# NanoCore.net
KiCad netlist of a schematic drawn in EasyEDA Pro
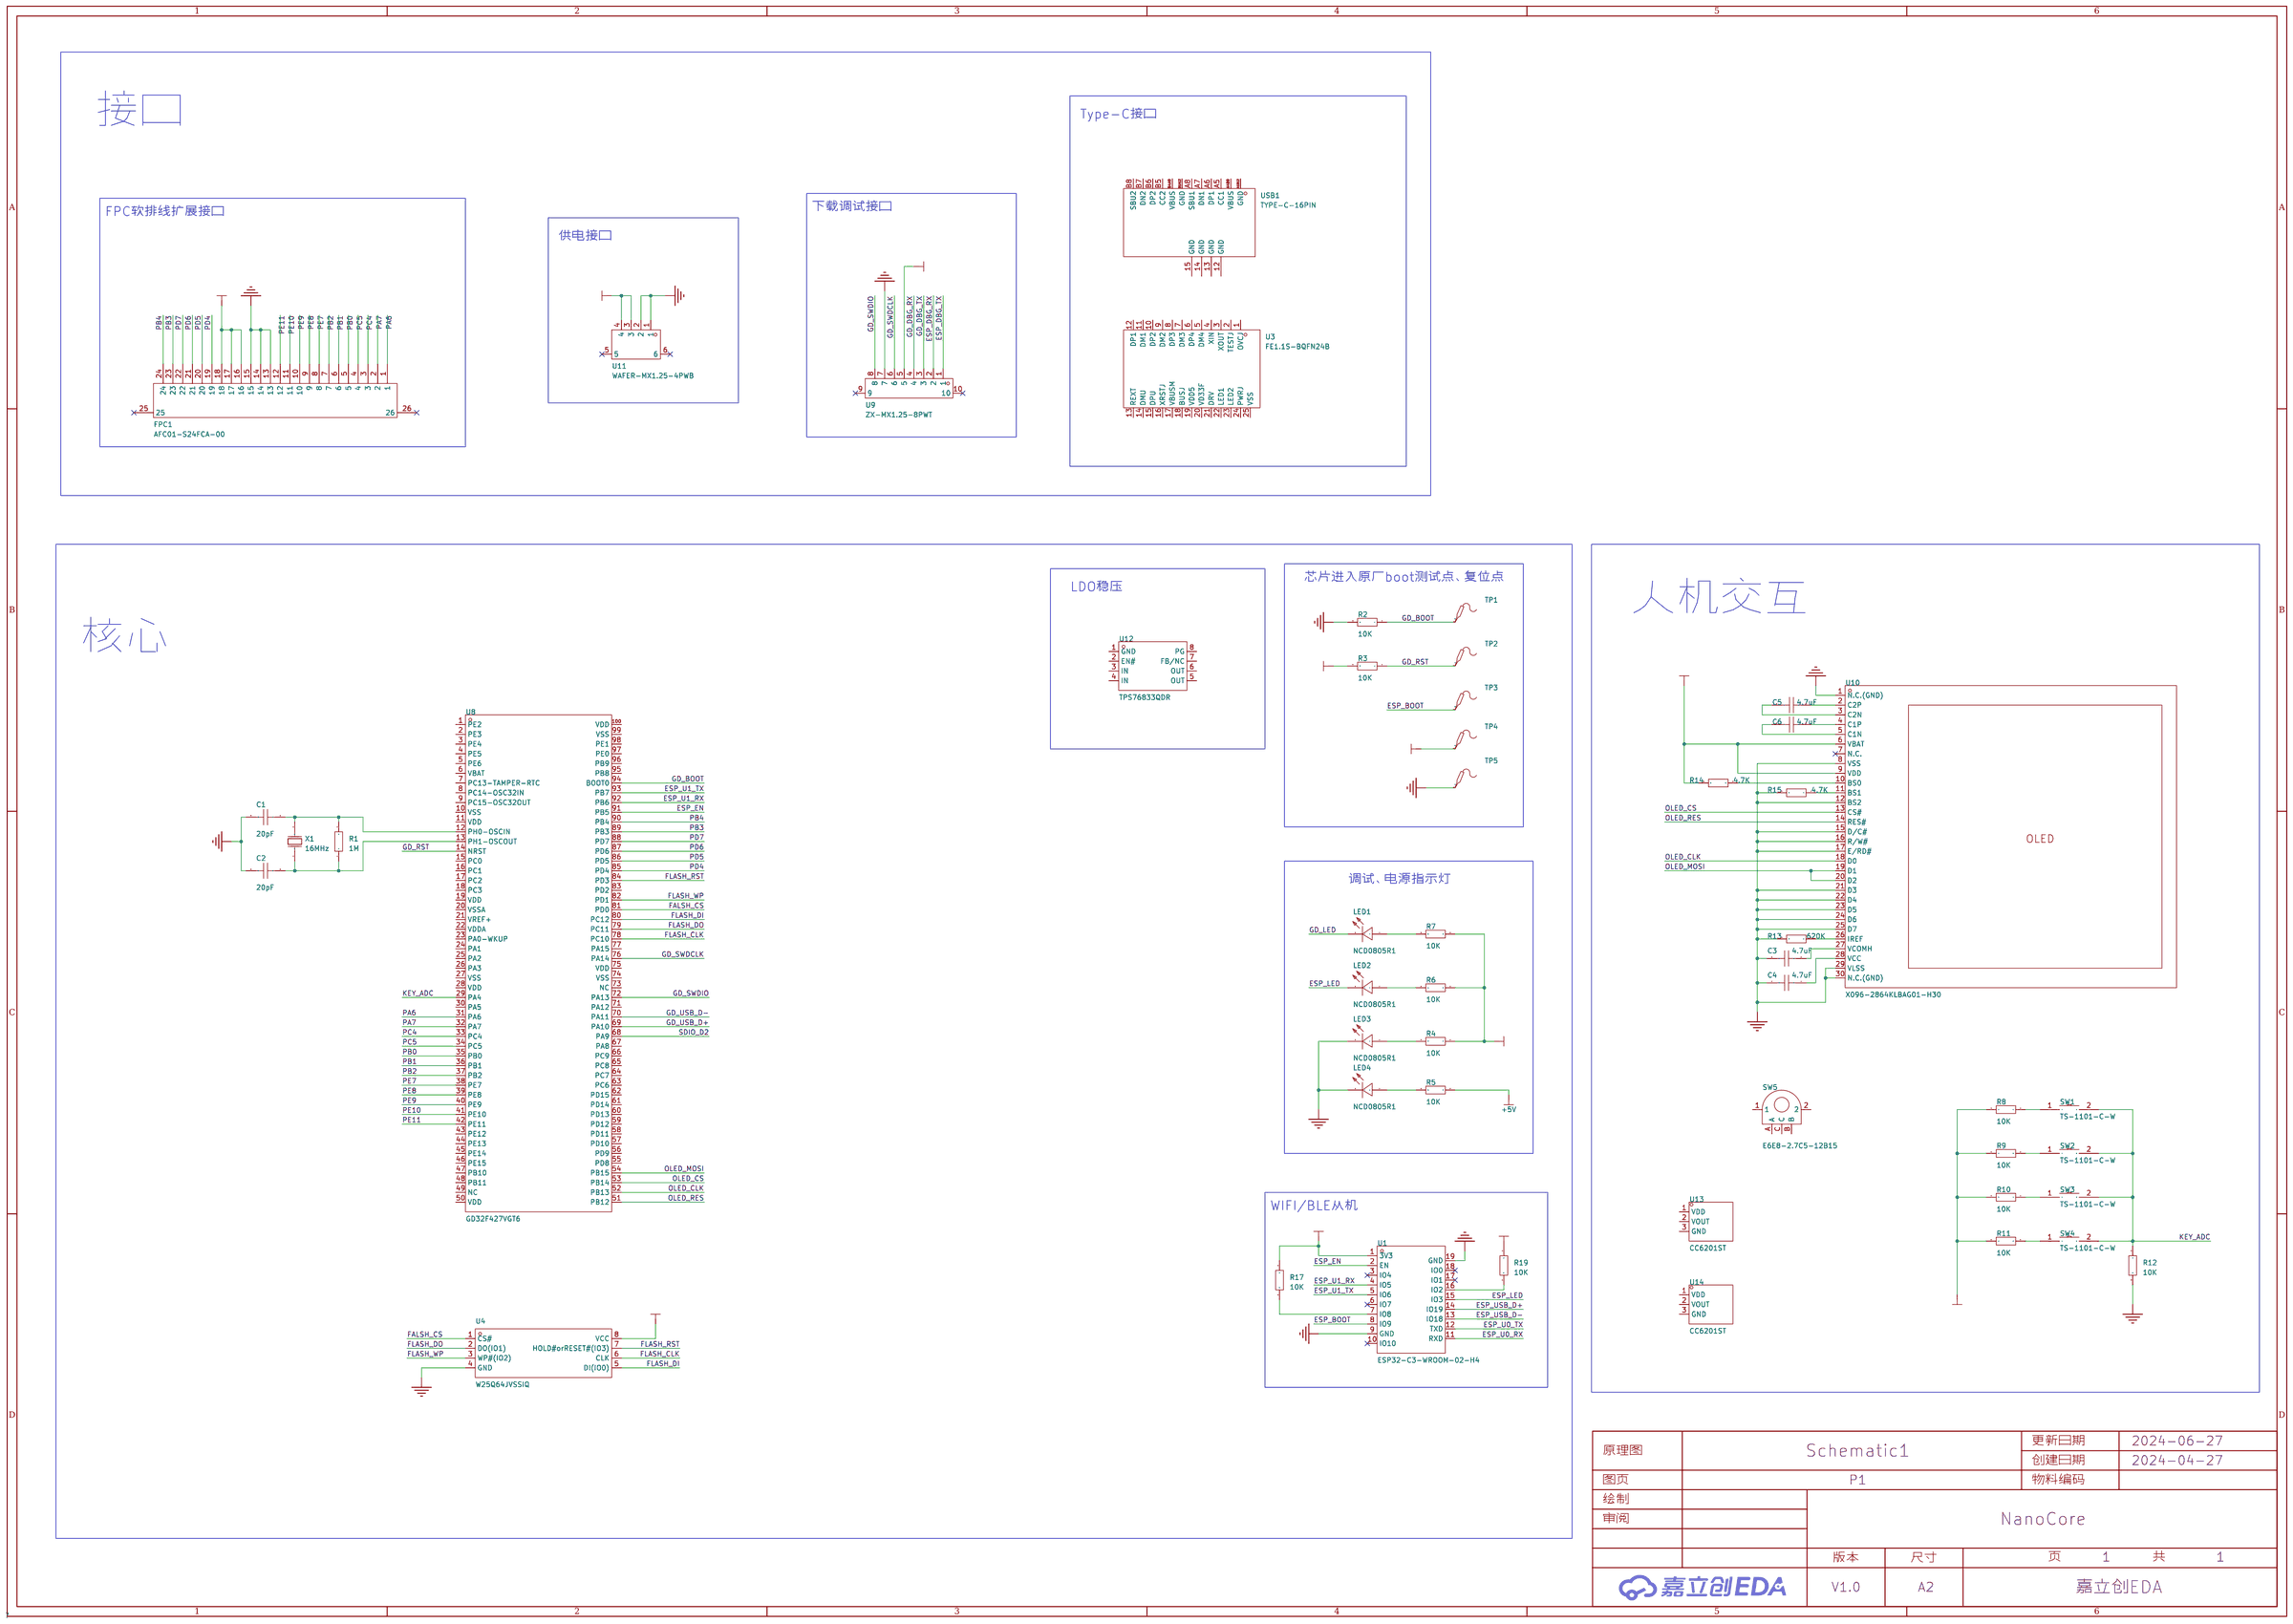
[diagram p0: schematic sheet]

(export (version "E")
  (design (tool "Eeschema 10.0.6"))
  (components
    (comp (ref "C1")
      (value "20pF")
      (footprint "easyedapro:C0603")
      (description "容值:100nF;精度:±10%;额定电压:50V;材质(温度系数):X7R;")
      (fields
        (field (name "Manufacturer Part") "CC0603KRX7R9BB104")
        (field (name "Manufacturer") "YAGEO(国巨)")
      )
      (libsource (lib "easyedapro") (part "CC0603KRX7R9BB104"))
    )
    (comp (ref "C2")
      (value "20pF")
      (footprint "easyedapro:C0603")
      (description "容值:100nF;精度:±10%;额定电压:50V;材质(温度系数):X7R;")
      (fields
        (field (name "Manufacturer Part") "CC0603KRX7R9BB104")
        (field (name "Manufacturer") "YAGEO(国巨)")
      )
      (libsource (lib "easyedapro") (part "CC0603KRX7R9BB104"))
    )
    (comp (ref "C3")
      (value "4.7uF")
      (footprint "easyedapro:C0603")
      (description "容值:100nF;精度:±10%;额定电压:50V;材质(温度系数):X7R;")
      (fields
        (field (name "Manufacturer Part") "CC0603KRX7R9BB104")
        (field (name "Manufacturer") "YAGEO(国巨)")
      )
      (libsource (lib "easyedapro") (part "CC0603KRX7R9BB104"))
    )
    (comp (ref "C4")
      (value "4.7uF")
      (footprint "easyedapro:C0603")
      (description "容值:100nF;精度:±10%;额定电压:50V;材质(温度系数):X7R;")
      (fields
        (field (name "Manufacturer Part") "CC0603KRX7R9BB104")
        (field (name "Manufacturer") "YAGEO(国巨)")
      )
      (libsource (lib "easyedapro") (part "CC0603KRX7R9BB104"))
    )
    (comp (ref "C5")
      (value "4.7uF")
      (footprint "easyedapro:C0603")
      (description "容值:100nF;精度:±10%;额定电压:50V;材质(温度系数):X7R;")
      (fields
        (field (name "Manufacturer Part") "CC0603KRX7R9BB104")
        (field (name "Manufacturer") "YAGEO(国巨)")
      )
      (libsource (lib "easyedapro") (part "CC0603KRX7R9BB104"))
    )
    (comp (ref "C6")
      (value "4.7uF")
      (footprint "easyedapro:C0603")
      (description "容值:100nF;精度:±10%;额定电压:50V;材质(温度系数):X7R;")
      (fields
        (field (name "Manufacturer Part") "CC0603KRX7R9BB104")
        (field (name "Manufacturer") "YAGEO(国巨)")
      )
      (libsource (lib "easyedapro") (part "CC0603KRX7R9BB104"))
    )
    (comp (ref "FPC1")
      (value "AFC01-S24FCA-00")
      (footprint "easyedapro:FPC-SMD_P0.50-24P_FGS-XJ-H2.0")
      (description "锁定特性:翻盖式;触点类型:下接;触点数量:24P;间距:0.5mm;安装类型:卧贴;")
      (fields (field (name "Manufacturer") "JS(钜硕电子)"))
      (libsource (lib "easyedapro") (part "AFC01-S24FCA-00"))
    )
    (comp (ref "LED1")
      (value "NCD0805R1")
      (footprint "easyedapro:LED0805-R-RD")
      (fields (field (name "Manufacturer") "国星光电"))
      (libsource (lib "easyedapro") (part "FC-2012HRK-620D"))
    )
    (comp (ref "LED2")
      (value "NCD0805R1")
      (footprint "easyedapro:LED0805-R-RD")
      (fields (field (name "Manufacturer") "国星光电"))
      (libsource (lib "easyedapro") (part "FC-2012HRK-620D"))
    )
    (comp (ref "LED3")
      (value "NCD0805R1")
      (footprint "easyedapro:LED0805-R-RD")
      (fields (field (name "Manufacturer") "国星光电"))
      (libsource (lib "easyedapro") (part "FC-2012HRK-620D"))
    )
    (comp (ref "LED4")
      (value "NCD0805R1")
      (footprint "easyedapro:LED0805-R-RD")
      (fields (field (name "Manufacturer") "国星光电"))
      (libsource (lib "easyedapro") (part "FC-2012HRK-620D"))
    )
    (comp (ref "R1")
      (value "1M")
      (footprint "easyedapro:R0805")
      (description "电阻类型:厚膜电阻;阻值:10kΩ;精度:±1%;功率:125mW;最大工作电压:150V;温度系数:±100ppm/°C;")
      (fields
        (field (name "Manufacturer Part") "0805W8F1002T5E")
        (field (name "Manufacturer") "UNI-ROYAL(厚声)")
      )
      (libsource (lib "easyedapro") (part "0805W8F1002T5E"))
    )
    (comp (ref "R2")
      (value "10K")
      (footprint "easyedapro:R0805")
      (description "电阻类型:厚膜电阻;阻值:10kΩ;精度:±1%;功率:125mW;最大工作电压:150V;温度系数:±100ppm/°C;")
      (fields
        (field (name "Manufacturer Part") "0805W8F1002T5E")
        (field (name "Manufacturer") "UNI-ROYAL(厚声)")
      )
      (libsource (lib "easyedapro") (part "0805W8F1002T5E"))
    )
    (comp (ref "R3")
      (value "10K")
      (footprint "easyedapro:R0805")
      (description "电阻类型:厚膜电阻;阻值:10kΩ;精度:±1%;功率:125mW;最大工作电压:150V;温度系数:±100ppm/°C;")
      (fields
        (field (name "Manufacturer Part") "0805W8F1002T5E")
        (field (name "Manufacturer") "UNI-ROYAL(厚声)")
      )
      (libsource (lib "easyedapro") (part "0805W8F1002T5E"))
    )
    (comp (ref "R4")
      (value "10K")
      (footprint "easyedapro:R0805")
      (description "电阻类型:厚膜电阻;阻值:10kΩ;精度:±1%;功率:125mW;最大工作电压:150V;温度系数:±100ppm/°C;")
      (fields
        (field (name "Manufacturer Part") "0805W8F1002T5E")
        (field (name "Manufacturer") "UNI-ROYAL(厚声)")
      )
      (libsource (lib "easyedapro") (part "0805W8F1002T5E"))
    )
    (comp (ref "R5")
      (value "10K")
      (footprint "easyedapro:R0805")
      (description "电阻类型:厚膜电阻;阻值:10kΩ;精度:±1%;功率:125mW;最大工作电压:150V;温度系数:±100ppm/°C;")
      (fields
        (field (name "Manufacturer Part") "0805W8F1002T5E")
        (field (name "Manufacturer") "UNI-ROYAL(厚声)")
      )
      (libsource (lib "easyedapro") (part "0805W8F1002T5E"))
    )
    (comp (ref "R6")
      (value "10K")
      (footprint "easyedapro:R0805")
      (description "电阻类型:厚膜电阻;阻值:10kΩ;精度:±1%;功率:125mW;最大工作电压:150V;温度系数:±100ppm/°C;")
      (fields
        (field (name "Manufacturer Part") "0805W8F1002T5E")
        (field (name "Manufacturer") "UNI-ROYAL(厚声)")
      )
      (libsource (lib "easyedapro") (part "0805W8F1002T5E"))
    )
    (comp (ref "R7")
      (value "10K")
      (footprint "easyedapro:R0805")
      (description "电阻类型:厚膜电阻;阻值:10kΩ;精度:±1%;功率:125mW;最大工作电压:150V;温度系数:±100ppm/°C;")
      (fields
        (field (name "Manufacturer Part") "0805W8F1002T5E")
        (field (name "Manufacturer") "UNI-ROYAL(厚声)")
      )
      (libsource (lib "easyedapro") (part "0805W8F1002T5E"))
    )
    (comp (ref "R8")
      (value "10K")
      (footprint "easyedapro:R0805")
      (description "电阻类型:厚膜电阻;阻值:10kΩ;精度:±1%;功率:125mW;最大工作电压:150V;温度系数:±100ppm/°C;")
      (fields
        (field (name "Manufacturer Part") "0805W8F1002T5E")
        (field (name "Manufacturer") "UNI-ROYAL(厚声)")
      )
      (libsource (lib "easyedapro") (part "0805W8F1002T5E"))
    )
    (comp (ref "R9")
      (value "10K")
      (footprint "easyedapro:R0805")
      (description "电阻类型:厚膜电阻;阻值:10kΩ;精度:±1%;功率:125mW;最大工作电压:150V;温度系数:±100ppm/°C;")
      (fields
        (field (name "Manufacturer Part") "0805W8F1002T5E")
        (field (name "Manufacturer") "UNI-ROYAL(厚声)")
      )
      (libsource (lib "easyedapro") (part "0805W8F1002T5E"))
    )
    (comp (ref "R10")
      (value "10K")
      (footprint "easyedapro:R0805")
      (description "电阻类型:厚膜电阻;阻值:10kΩ;精度:±1%;功率:125mW;最大工作电压:150V;温度系数:±100ppm/°C;")
      (fields
        (field (name "Manufacturer Part") "0805W8F1002T5E")
        (field (name "Manufacturer") "UNI-ROYAL(厚声)")
      )
      (libsource (lib "easyedapro") (part "0805W8F1002T5E"))
    )
    (comp (ref "R11")
      (value "10K")
      (footprint "easyedapro:R0805")
      (description "电阻类型:厚膜电阻;阻值:10kΩ;精度:±1%;功率:125mW;最大工作电压:150V;温度系数:±100ppm/°C;")
      (fields
        (field (name "Manufacturer Part") "0805W8F1002T5E")
        (field (name "Manufacturer") "UNI-ROYAL(厚声)")
      )
      (libsource (lib "easyedapro") (part "0805W8F1002T5E"))
    )
    (comp (ref "R12")
      (value "10K")
      (footprint "easyedapro:R0805")
      (description "电阻类型:厚膜电阻;阻值:10kΩ;精度:±1%;功率:125mW;最大工作电压:150V;温度系数:±100ppm/°C;")
      (fields
        (field (name "Manufacturer Part") "0805W8F1002T5E")
        (field (name "Manufacturer") "UNI-ROYAL(厚声)")
      )
      (libsource (lib "easyedapro") (part "0805W8F1002T5E"))
    )
    (comp (ref "R13")
      (value "620K")
      (footprint "easyedapro:R0805")
      (description "电阻类型:厚膜电阻;阻值:10kΩ;精度:±1%;功率:125mW;最大工作电压:150V;温度系数:±100ppm/°C;")
      (fields
        (field (name "Manufacturer Part") "0805W8F1002T5E")
        (field (name "Manufacturer") "UNI-ROYAL(厚声)")
      )
      (libsource (lib "easyedapro") (part "0805W8F1002T5E"))
    )
    (comp (ref "R14")
      (value "4.7K")
      (footprint "easyedapro:R0805")
      (description "电阻类型:厚膜电阻;阻值:10kΩ;精度:±1%;功率:125mW;最大工作电压:150V;温度系数:±100ppm/°C;")
      (fields
        (field (name "Manufacturer Part") "0805W8F1002T5E")
        (field (name "Manufacturer") "UNI-ROYAL(厚声)")
      )
      (libsource (lib "easyedapro") (part "0805W8F1002T5E"))
    )
    (comp (ref "R15")
      (value "4.7K")
      (footprint "easyedapro:R0805")
      (description "电阻类型:厚膜电阻;阻值:10kΩ;精度:±1%;功率:125mW;最大工作电压:150V;温度系数:±100ppm/°C;")
      (fields
        (field (name "Manufacturer Part") "0805W8F1002T5E")
        (field (name "Manufacturer") "UNI-ROYAL(厚声)")
      )
      (libsource (lib "easyedapro") (part "0805W8F1002T5E"))
    )
    (comp (ref "R17")
      (value "10K")
      (footprint "easyedapro:R0805")
      (description "电阻类型:厚膜电阻;阻值:10kΩ;精度:±1%;功率:125mW;最大工作电压:150V;温度系数:±100ppm/°C;")
      (fields
        (field (name "Manufacturer Part") "0805W8F1002T5E")
        (field (name "Manufacturer") "UNI-ROYAL(厚声)")
      )
      (libsource (lib "easyedapro") (part "0805W8F1002T5E"))
    )
    (comp (ref "R19")
      (value "10K")
      (footprint "easyedapro:R0805")
      (description "电阻类型:厚膜电阻;阻值:10kΩ;精度:±1%;功率:125mW;最大工作电压:150V;温度系数:±100ppm/°C;")
      (fields
        (field (name "Manufacturer Part") "0805W8F1002T5E")
        (field (name "Manufacturer") "UNI-ROYAL(厚声)")
      )
      (libsource (lib "easyedapro") (part "0805W8F1002T5E"))
    )
    (comp (ref "SW1")
      (value "TS-1101-C-W")
      (footprint "easyedapro:SW-SMD_L6.0-W3.3-LS8.0")
      (fields (field (name "Manufacturer") "XKB Connectivity(中国星坤)"))
      (libsource (lib "easyedapro") (part "TS-1101-C-W"))
    )
    (comp (ref "SW2")
      (value "TS-1101-C-W")
      (footprint "easyedapro:SW-SMD_L6.0-W3.3-LS8.0")
      (fields (field (name "Manufacturer") "XKB Connectivity(中国星坤)"))
      (libsource (lib "easyedapro") (part "TS-1101-C-W"))
    )
    (comp (ref "SW3")
      (value "TS-1101-C-W")
      (footprint "easyedapro:SW-SMD_L6.0-W3.3-LS8.0")
      (fields (field (name "Manufacturer") "XKB Connectivity(中国星坤)"))
      (libsource (lib "easyedapro") (part "TS-1101-C-W"))
    )
    (comp (ref "SW4")
      (value "TS-1101-C-W")
      (footprint "easyedapro:SW-SMD_L6.0-W3.3-LS8.0")
      (fields (field (name "Manufacturer") "XKB Connectivity(中国星坤)"))
      (libsource (lib "easyedapro") (part "TS-1101-C-W"))
    )
    (comp (ref "SW5")
      (value "E6E8-2.7C5-12B15")
      (footprint "easyedapro:SW-SMD_L5.7-W5.7-P2.00-LS6.9")
      (description "EC05E超小型编码器-有齿感")
      (fields (field (name "Manufacturer") "G-Switch(品赞)"))
      (libsource (lib "easyedapro") (part "E6E8-2.7C5-12B15"))
    )
    (comp (ref "TP1")
      (value "~")
      (footprint "easyedapro:Test-Point-0.5mm")
      (description "Test Point 测试点")
      (libsource (lib "easyedapro") (part "Test-Point"))
    )
    (comp (ref "TP2")
      (value "~")
      (footprint "easyedapro:Test-Point-0.5mm")
      (description "Test Point 测试点")
      (libsource (lib "easyedapro") (part "Test-Point"))
    )
    (comp (ref "TP3")
      (value "~")
      (footprint "easyedapro:Test-Point-0.5mm")
      (description "Test Point 测试点")
      (libsource (lib "easyedapro") (part "Test-Point"))
    )
    (comp (ref "TP4")
      (value "~")
      (footprint "easyedapro:Test-Point-0.5mm")
      (description "Test Point 测试点")
      (libsource (lib "easyedapro") (part "Test-Point"))
    )
    (comp (ref "TP5")
      (value "~")
      (footprint "easyedapro:Test-Point-0.5mm")
      (description "Test Point 测试点")
      (libsource (lib "easyedapro") (part "Test-Point"))
    )
    (comp (ref "U1")
      (value "ESP32-C3-WROOM-02-H4")
      (footprint "easyedapro:WIFIM-SMD_18P-L20.0-W18.0-P1.50")
      (fields (field (name "Manufacturer") "ESPRESSIF(乐鑫)"))
      (libsource (lib "easyedapro") (part "ESP32-C3-WROOM-02-H4"))
    )
    (comp (ref "U3")
      (value "FE1.1S-BQFN24B")
      (footprint "easyedapro:WQFN-24_L4.0-W4.0-P0.50-TL-EP2.7")
      (fields (field (name "Manufacturer") "TERMINUS"))
      (libsource (lib "easyedapro") (part "FE1.1S-BQFN24B"))
    )
    (comp (ref "U4")
      (value "W25Q64JVSSIQ")
      (footprint "easyedapro:SOIC-8_L5.3-W5.3-P1.27-LS8.0-BL")
      (fields (field (name "Manufacturer") "WINBOND(华邦)"))
      (libsource (lib "easyedapro") (part "W25Q64JVSSIQ_C179171"))
    )
    (comp (ref "U8")
      (value "GD32F427VGT6")
      (footprint "easyedapro:LQFP-100_L14.0-W14.0-P0.50-LS16.0-TL")
      (description "CPU内核:CM4;程序存储容量:1MB;RAM总容量:256KB;GPIO端口数量:82;工作电压范围:-;CPU最大主频:200MHz;程序存储器类型:FLASH;")
      (fields (field (name "Manufacturer") "GigaDevice(兆易创新)"))
      (libsource (lib "easyedapro") (part "GD32F427VGT6"))
    )
    (comp (ref "U9")
      (value "ZX-MX1.25-8PWT")
      (footprint "easyedapro:CONN-SMD_8P-P1.25_ZX-MX1.25-8PWT")
      (fields (field (name "Manufacturer") "Megastar(兆星)"))
      (libsource (lib "easyedapro") (part "ZX-MX1.25-8PWT"))
    )
    (comp (ref "U10")
      (value "X096-2864KLBAG01-H30")
      (footprint "easyedapro:OLED-SMD_X096-2864KLBAG01-H30")
      (description "主控芯片:SSD1315;尺寸(inch):0.96;像素分辨率:128x64;")
      (fields (field (name "Manufacturer") "Newvision(新智景)"))
      (libsource (lib "easyedapro") (part "X096-2864KLBAG01-H30"))
    )
    (comp (ref "U11")
      (value "WAFER-MX1.25-4PWB")
      (footprint "easyedapro:CONN-SMD_4P-P1.25_WAFER-MX1.25-4PWB")
      (description "插针结构:1x4P;间距:1.25mm;安装方式:卧贴;总PIN数:4P;排数:1;每排PIN数:4;额定电流:1A;工作温度范围:-25°C~+85°C;")
      (fields (field (name "Manufacturer") "XUNPU(讯普)"))
      (libsource (lib "easyedapro") (part "WAFER-MX1.25-4PWB"))
    )
    (comp (ref "U12")
      (value "TPS76833QDR")
      (footprint "easyedapro:SOIC-8_L4.9-W3.9-P1.27-LS6.0-BL")
      (description "输出类型:固定;最大输入电压:10V;输出电压:3.3V;输出电流:1A;电源纹波抑制比(PSRR):60dB@(1kHz);输出极性:正极;")
      (fields (field (name "Manufacturer") "TI(德州仪器)"))
      (libsource (lib "easyedapro") (part "TPS76833QDR"))
    )
    (comp (ref "U13")
      (value "CC6201ST")
      (footprint "easyedapro:SOT-23-3_L2.9-W1.3-P1.90-LS2.4-BR")
      (description "微功耗   全极型微功耗霍尔效应开关")
      (fields (field (name "Manufacturer") "CrossChip(成都芯进)"))
      (libsource (lib "easyedapro") (part "CC6201ST"))
    )
    (comp (ref "U14")
      (value "CC6201ST")
      (footprint "easyedapro:SOT-23-3_L2.9-W1.3-P1.90-LS2.4-BR")
      (description "微功耗   全极型微功耗霍尔效应开关")
      (fields (field (name "Manufacturer") "CrossChip(成都芯进)"))
      (libsource (lib "easyedapro") (part "CC6201ST"))
    )
    (comp (ref "USB1")
      (value "TYPE-C-16PIN")
      (footprint "easyedapro:USB-SMD_TYPEC-16PIN")
      (libsource (lib "easyedapro") (part "CONNECTOR,USB,TYPEC,RTANG,16PIN"))
    )
    (comp (ref "X1")
      (value "16MHz")
      (footprint "easyedapro:CRYSTAL-SMD_L5.0-W3.2")
      (description "晶振类型:贴片晶振;频率:8MHz;常温频差:±10ppm;外接负载电容:20pF;频率稳定度(全温):±20ppm;")
      (fields (field (name "Manufacturer Part") "X50328MSB2GI") (field (name "Manufacturer") "YXC(扬兴晶振)"))
      (libsource (lib "easyedapro") (part "X50328MSB2GI"))
    )
  )
  (nets
    (net (code "1") (name "+5V") (class "Default")
      (node (ref "R5") (pin "1") (pinfunction "1_1") (pintype "input"))
    )
    (net (code "2") (name "/ESP_BOOT") (class "Default")
      (node (ref "TP3") (pin "1") (pinfunction "1_1") (pintype "input"))
      (node (ref "U1") (pin "8") (pinfunction "IO9_8") (pintype "unspecified"))
    )
    (net (code "3") (name "/ESP_DBG_RX") (class "Default")
      (node (ref "U9") (pin "2") (pinfunction "2_2") (pintype "unspecified"))
    )
    (net (code "4") (name "/ESP_DBG_TX") (class "Default")
      (node (ref "U9") (pin "1") (pinfunction "1_1") (pintype "unspecified"))
    )
    (net (code "5") (name "/ESP_EN") (class "Default")
      (node (ref "U1") (pin "2") (pinfunction "EN_2") (pintype "unspecified"))
      (node (ref "U8") (pin "91") (pinfunction "PB5_91") (pintype "unspecified"))
    )
    (net (code "6") (name "/ESP_LED") (class "Default")
      (node (ref "LED2") (pin "2") (pinfunction "-_2") (pintype "unspecified"))
      (node (ref "U1") (pin "15") (pinfunction "IO3_15") (pintype "unspecified"))
    )
    (net (code "7") (name "/ESP_U0_RX") (class "Default")
      (node (ref "U1") (pin "11") (pinfunction "RXD_11") (pintype "unspecified"))
    )
    (net (code "8") (name "/ESP_U0_TX") (class "Default")
      (node (ref "U1") (pin "12") (pinfunction "TXD_12") (pintype "unspecified"))
    )
    (net (code "9") (name "/ESP_U1_RX") (class "Default")
      (node (ref "U1") (pin "4") (pinfunction "IO5_4") (pintype "unspecified"))
      (node (ref "U8") (pin "92") (pinfunction "PB6_92") (pintype "unspecified"))
    )
    (net (code "10") (name "/ESP_U1_TX") (class "Default")
      (node (ref "U1") (pin "5") (pinfunction "IO6_5") (pintype "unspecified"))
      (node (ref "U8") (pin "93") (pinfunction "PB7_93") (pintype "unspecified"))
    )
    (net (code "11") (name "/ESP_USB_D+") (class "Default")
      (node (ref "U1") (pin "14") (pinfunction "IO19_14") (pintype "unspecified"))
    )
    (net (code "12") (name "/ESP_USB_D-") (class "Default")
      (node (ref "U1") (pin "13") (pinfunction "IO18_13") (pintype "unspecified"))
    )
    (net (code "13") (name "/FALSH_CS") (class "Default")
      (node (ref "U4") (pin "1") (pinfunction "CS#_1") (pintype "unspecified"))
      (node (ref "U8") (pin "81") (pinfunction "PD0_81") (pintype "unspecified"))
    )
    (net (code "14") (name "/FLASH_CLK") (class "Default")
      (node (ref "U4") (pin "6") (pinfunction "CLK_6") (pintype "unspecified"))
      (node (ref "U8") (pin "78") (pinfunction "PC10_78") (pintype "unspecified"))
    )
    (net (code "15") (name "/FLASH_DI") (class "Default")
      (node (ref "U4") (pin "5") (pinfunction "DI(IO0)_5") (pintype "unspecified"))
      (node (ref "U8") (pin "80") (pinfunction "PC12_80") (pintype "unspecified"))
    )
    (net (code "16") (name "/FLASH_DO") (class "Default")
      (node (ref "U4") (pin "2") (pinfunction "DO(IO1)_2") (pintype "unspecified"))
      (node (ref "U8") (pin "79") (pinfunction "PC11_79") (pintype "unspecified"))
    )
    (net (code "17") (name "/FLASH_RST") (class "Default")
      (node (ref "U4") (pin "7") (pinfunction "HOLD#orRESET#(IO3)_7") (pintype "unspecified"))
      (node (ref "U8") (pin "84") (pinfunction "PD3_84") (pintype "unspecified"))
    )
    (net (code "18") (name "/FLASH_WP") (class "Default")
      (node (ref "U4") (pin "3") (pinfunction "WP#(IO2)_3") (pintype "unspecified"))
      (node (ref "U8") (pin "82") (pinfunction "PD1_82") (pintype "unspecified"))
    )
    (net (code "19") (name "/GD_BOOT") (class "Default")
      (node (ref "R2") (pin "1") (pinfunction "1_1") (pintype "input"))
      (node (ref "TP1") (pin "1") (pinfunction "1_1") (pintype "input"))
      (node (ref "U8") (pin "94") (pinfunction "BOOT0_94") (pintype "unspecified"))
    )
    (net (code "20") (name "/GD_DBG_RX") (class "Default")
      (node (ref "U9") (pin "4") (pinfunction "4_4") (pintype "unspecified"))
    )
    (net (code "21") (name "/GD_DBG_TX") (class "Default")
      (node (ref "U9") (pin "3") (pinfunction "3_3") (pintype "unspecified"))
    )
    (net (code "22") (name "/GD_LED") (class "Default")
      (node (ref "LED1") (pin "2") (pinfunction "-_2") (pintype "unspecified"))
    )
    (net (code "23") (name "/GD_RST") (class "Default")
      (node (ref "R3") (pin "1") (pinfunction "1_1") (pintype "input"))
      (node (ref "TP2") (pin "1") (pinfunction "1_1") (pintype "input"))
      (node (ref "U8") (pin "14") (pinfunction "NRST_14") (pintype "unspecified"))
    )
    (net (code "24") (name "/GD_SWDCLK") (class "Default")
      (node (ref "U8") (pin "76") (pinfunction "PA14_76") (pintype "unspecified"))
      (node (ref "U9") (pin "6") (pinfunction "6_6") (pintype "unspecified"))
    )
    (net (code "25") (name "/GD_SWDIO") (class "Default")
      (node (ref "U8") (pin "72") (pinfunction "PA13_72") (pintype "unspecified"))
      (node (ref "U9") (pin "8") (pinfunction "8_8") (pintype "unspecified"))
    )
    (net (code "26") (name "/GD_USB_D+") (class "Default")
      (node (ref "U8") (pin "69") (pinfunction "PA10_69") (pintype "unspecified"))
    )
    (net (code "27") (name "/GD_USB_D-") (class "Default")
      (node (ref "U8") (pin "70") (pinfunction "PA11_70") (pintype "unspecified"))
    )
    (net (code "28") (name "/KEY_ADC") (class "Default")
      (node (ref "R12") (pin "1") (pinfunction "1_1") (pintype "input"))
      (node (ref "SW1") (pin "2") (pinfunction "2_2") (pintype "unspecified"))
      (node (ref "SW2") (pin "2") (pinfunction "2_2") (pintype "unspecified"))
      (node (ref "SW3") (pin "2") (pinfunction "2_2") (pintype "unspecified"))
      (node (ref "SW4") (pin "2") (pinfunction "2_2") (pintype "unspecified"))
      (node (ref "U8") (pin "29") (pinfunction "PA4_29") (pintype "unspecified"))
    )
    (net (code "29") (name "/OLED_CLK") (class "Default")
      (node (ref "U10") (pin "18") (pinfunction "D0_18") (pintype "unspecified"))
      (node (ref "U8") (pin "52") (pinfunction "PB13_52") (pintype "unspecified"))
    )
    (net (code "30") (name "/OLED_CS") (class "Default")
      (node (ref "U10") (pin "13") (pinfunction "CS#_13") (pintype "unspecified"))
      (node (ref "U8") (pin "53") (pinfunction "PB14_53") (pintype "unspecified"))
    )
    (net (code "31") (name "/OLED_MOSI") (class "Default")
      (node (ref "U10") (pin "19") (pinfunction "D1_19") (pintype "unspecified"))
      (node (ref "U10") (pin "20") (pinfunction "D2_20") (pintype "unspecified"))
      (node (ref "U8") (pin "54") (pinfunction "PB15_54") (pintype "unspecified"))
    )
    (net (code "32") (name "/OLED_RES") (class "Default")
      (node (ref "U10") (pin "14") (pinfunction "RES#_14") (pintype "unspecified"))
      (node (ref "U8") (pin "51") (pinfunction "PB12_51") (pintype "unspecified"))
    )
    (net (code "33") (name "/PA6") (class "Default")
      (node (ref "FPC1") (pin "1") (pinfunction "1_1") (pintype "unspecified"))
      (node (ref "U8") (pin "31") (pinfunction "PA6_31") (pintype "unspecified"))
    )
    (net (code "34") (name "/PA7") (class "Default")
      (node (ref "FPC1") (pin "2") (pinfunction "2_2") (pintype "unspecified"))
      (node (ref "U8") (pin "32") (pinfunction "PA7_32") (pintype "unspecified"))
    )
    (net (code "35") (name "/PB0") (class "Default")
      (node (ref "FPC1") (pin "5") (pinfunction "5_5") (pintype "unspecified"))
      (node (ref "U8") (pin "35") (pinfunction "PB0_35") (pintype "unspecified"))
    )
    (net (code "36") (name "/PB1") (class "Default")
      (node (ref "FPC1") (pin "6") (pinfunction "6_6") (pintype "unspecified"))
      (node (ref "U8") (pin "36") (pinfunction "PB1_36") (pintype "unspecified"))
    )
    (net (code "37") (name "/PB2") (class "Default")
      (node (ref "FPC1") (pin "7") (pinfunction "7_7") (pintype "unspecified"))
      (node (ref "U8") (pin "37") (pinfunction "PB2_37") (pintype "unspecified"))
    )
    (net (code "38") (name "/PB3") (class "Default")
      (node (ref "FPC1") (pin "23") (pinfunction "23_23") (pintype "unspecified"))
      (node (ref "U8") (pin "89") (pinfunction "PB3_89") (pintype "unspecified"))
    )
    (net (code "39") (name "/PB4") (class "Default")
      (node (ref "FPC1") (pin "24") (pinfunction "24_24") (pintype "unspecified"))
      (node (ref "U8") (pin "90") (pinfunction "PB4_90") (pintype "unspecified"))
    )
    (net (code "40") (name "/PC4") (class "Default")
      (node (ref "FPC1") (pin "3") (pinfunction "3_3") (pintype "unspecified"))
      (node (ref "U8") (pin "33") (pinfunction "PC4_33") (pintype "unspecified"))
    )
    (net (code "41") (name "/PC5") (class "Default")
      (node (ref "FPC1") (pin "4") (pinfunction "4_4") (pintype "unspecified"))
      (node (ref "U8") (pin "34") (pinfunction "PC5_34") (pintype "unspecified"))
    )
    (net (code "42") (name "/PD4") (class "Default")
      (node (ref "FPC1") (pin "19") (pinfunction "19_19") (pintype "unspecified"))
      (node (ref "U8") (pin "85") (pinfunction "PD4_85") (pintype "unspecified"))
    )
    (net (code "43") (name "/PD5") (class "Default")
      (node (ref "FPC1") (pin "20") (pinfunction "20_20") (pintype "unspecified"))
      (node (ref "U8") (pin "86") (pinfunction "PD5_86") (pintype "unspecified"))
    )
    (net (code "44") (name "/PD6") (class "Default")
      (node (ref "FPC1") (pin "21") (pinfunction "21_21") (pintype "unspecified"))
      (node (ref "U8") (pin "87") (pinfunction "PD6_87") (pintype "unspecified"))
    )
    (net (code "45") (name "/PD7") (class "Default")
      (node (ref "FPC1") (pin "22") (pinfunction "22_22") (pintype "unspecified"))
      (node (ref "U8") (pin "88") (pinfunction "PD7_88") (pintype "unspecified"))
    )
    (net (code "46") (name "/PE7") (class "Default")
      (node (ref "FPC1") (pin "8") (pinfunction "8_8") (pintype "unspecified"))
      (node (ref "U8") (pin "38") (pinfunction "PE7_38") (pintype "unspecified"))
    )
    (net (code "47") (name "/PE8") (class "Default")
      (node (ref "FPC1") (pin "9") (pinfunction "9_9") (pintype "unspecified"))
      (node (ref "U8") (pin "39") (pinfunction "PE8_39") (pintype "unspecified"))
    )
    (net (code "48") (name "/PE9") (class "Default")
      (node (ref "FPC1") (pin "10") (pinfunction "10_10") (pintype "unspecified"))
      (node (ref "U8") (pin "40") (pinfunction "PE9_40") (pintype "unspecified"))
    )
    (net (code "49") (name "/PE10") (class "Default")
      (node (ref "FPC1") (pin "11") (pinfunction "11_11") (pintype "unspecified"))
      (node (ref "U8") (pin "41") (pinfunction "PE10_41") (pintype "unspecified"))
    )
    (net (code "50") (name "/PE11") (class "Default")
      (node (ref "FPC1") (pin "12") (pinfunction "12_12") (pintype "unspecified"))
      (node (ref "U8") (pin "42") (pinfunction "PE11_42") (pintype "unspecified"))
    )
    (net (code "51") (name "/SDIO_D2") (class "Default")
      (node (ref "U8") (pin "68") (pinfunction "PA9_68") (pintype "unspecified"))
    )
    (net (code "52") (name "GND") (class "Default")
      (node (ref "C1") (pin "2") (pinfunction "2_2") (pintype "unspecified"))
      (node (ref "C2") (pin "2") (pinfunction "2_2") (pintype "unspecified"))
      (node (ref "C3") (pin "2") (pinfunction "2_2") (pintype "unspecified"))
      (node (ref "C4") (pin "2") (pinfunction "2_2") (pintype "unspecified"))
      (node (ref "FPC1") (pin "13") (pinfunction "13_13") (pintype "unspecified"))
      (node (ref "FPC1") (pin "14") (pinfunction "14_14") (pintype "unspecified"))
      (node (ref "FPC1") (pin "15") (pinfunction "15_15") (pintype "unspecified"))
      (node (ref "LED3") (pin "2") (pinfunction "-_2") (pintype "unspecified"))
      (node (ref "LED4") (pin "2") (pinfunction "-_2") (pintype "unspecified"))
      (node (ref "R12") (pin "2") (pinfunction "2_2") (pintype "input"))
      (node (ref "R13") (pin "2") (pinfunction "2_2") (pintype "input"))
      (node (ref "R15") (pin "2") (pinfunction "2_2") (pintype "input"))
      (node (ref "R2") (pin "2") (pinfunction "2_2") (pintype "input"))
      (node (ref "TP5") (pin "1") (pinfunction "1_1") (pintype "input"))
      (node (ref "U1") (pin "19") (pinfunction "GND_19") (pintype "unspecified"))
      (node (ref "U1") (pin "9") (pinfunction "GND_9") (pintype "unspecified"))
      (node (ref "U10") (pin "1") (pinfunction "N.C.(GND)_1") (pintype "unspecified"))
      (node (ref "U10") (pin "12") (pinfunction "BS2_12") (pintype "unspecified"))
      (node (ref "U10") (pin "15") (pinfunction "D/C#_15") (pintype "unspecified"))
      (node (ref "U10") (pin "16") (pinfunction "R/W#_16") (pintype "unspecified"))
      (node (ref "U10") (pin "17") (pinfunction "E/RD#_17") (pintype "unspecified"))
      (node (ref "U10") (pin "21") (pinfunction "D3_21") (pintype "unspecified"))
      (node (ref "U10") (pin "22") (pinfunction "D4_22") (pintype "unspecified"))
      (node (ref "U10") (pin "23") (pinfunction "D5_23") (pintype "unspecified"))
      (node (ref "U10") (pin "24") (pinfunction "D6_24") (pintype "unspecified"))
      (node (ref "U10") (pin "25") (pinfunction "D7_25") (pintype "unspecified"))
      (node (ref "U10") (pin "29") (pinfunction "VLSS_29") (pintype "unspecified"))
      (node (ref "U10") (pin "30") (pinfunction "N.C.(GND)_30") (pintype "unspecified"))
      (node (ref "U10") (pin "8") (pinfunction "VSS_8") (pintype "unspecified"))
      (node (ref "U11") (pin "1") (pinfunction "1_1") (pintype "unspecified"))
      (node (ref "U11") (pin "2") (pinfunction "2_2") (pintype "unspecified"))
      (node (ref "U4") (pin "4") (pinfunction "GND_4") (pintype "unspecified"))
      (node (ref "U9") (pin "7") (pinfunction "7_7") (pintype "unspecified"))
    )
    (net (code "53") (name "Net-(LED1-+)") (class "Default")
      (node (ref "LED1") (pin "1") (pinfunction "+_1") (pintype "unspecified"))
      (node (ref "R7") (pin "2") (pinfunction "2_2") (pintype "input"))
    )
    (net (code "54") (name "Net-(LED2-+)") (class "Default")
      (node (ref "LED2") (pin "1") (pinfunction "+_1") (pintype "unspecified"))
      (node (ref "R6") (pin "2") (pinfunction "2_2") (pintype "input"))
    )
    (net (code "55") (name "Net-(LED3-+)") (class "Default")
      (node (ref "LED3") (pin "1") (pinfunction "+_1") (pintype "unspecified"))
      (node (ref "R4") (pin "2") (pinfunction "2_2") (pintype "input"))
    )
    (net (code "56") (name "Net-(LED4-+)") (class "Default")
      (node (ref "LED4") (pin "1") (pinfunction "+_1") (pintype "unspecified"))
      (node (ref "R5") (pin "2") (pinfunction "2_2") (pintype "input"))
    )
    (net (code "57") (name "Net-(R8-Pad1)") (class "Default")
      (node (ref "R8") (pin "1") (pinfunction "1_1") (pintype "input"))
      (node (ref "SW1") (pin "1") (pinfunction "1_1") (pintype "unspecified"))
    )
    (net (code "58") (name "Net-(R9-Pad1)") (class "Default")
      (node (ref "R9") (pin "1") (pinfunction "1_1") (pintype "input"))
      (node (ref "SW2") (pin "1") (pinfunction "1_1") (pintype "unspecified"))
    )
    (net (code "59") (name "Net-(R10-Pad1)") (class "Default")
      (node (ref "R10") (pin "1") (pinfunction "1_1") (pintype "input"))
      (node (ref "SW3") (pin "1") (pinfunction "1_1") (pintype "unspecified"))
    )
    (net (code "60") (name "Net-(R11-Pad1)") (class "Default")
      (node (ref "R11") (pin "1") (pinfunction "1_1") (pintype "input"))
      (node (ref "SW4") (pin "1") (pinfunction "1_1") (pintype "unspecified"))
    )
    (net (code "61") (name "Net-(U1-IO2)") (class "Default")
      (node (ref "R19") (pin "2") (pinfunction "2_2") (pintype "input"))
      (node (ref "U1") (pin "16") (pinfunction "IO2_16") (pintype "unspecified"))
    )
    (net (code "62") (name "Net-(U1-IO8)") (class "Default")
      (node (ref "R17") (pin "2") (pinfunction "2_2") (pintype "input"))
      (node (ref "U1") (pin "7") (pinfunction "IO8_7") (pintype "unspecified"))
    )
    (net (code "63") (name "Net-(U8-PH0-OSCIN)") (class "Default")
      (node (ref "C1") (pin "1") (pinfunction "1_1") (pintype "unspecified"))
      (node (ref "R1") (pin "2") (pinfunction "2_2") (pintype "input"))
      (node (ref "U8") (pin "12") (pinfunction "PH0-OSCIN_12") (pintype "unspecified"))
      (node (ref "X1") (pin "2") (pinfunction "OSC2_2") (pintype "input"))
    )
    (net (code "64") (name "Net-(U8-PH1-OSCOUT)") (class "Default")
      (node (ref "C2") (pin "1") (pinfunction "1_1") (pintype "unspecified"))
      (node (ref "R1") (pin "1") (pinfunction "1_1") (pintype "input"))
      (node (ref "U8") (pin "13") (pinfunction "PH1-OSCOUT_13") (pintype "unspecified"))
      (node (ref "X1") (pin "1") (pinfunction "OSC1_1") (pintype "input"))
    )
    (net (code "65") (name "Net-(U10-BS0)") (class "Default")
      (node (ref "R14") (pin "1") (pinfunction "1_1") (pintype "input"))
      (node (ref "U10") (pin "10") (pinfunction "BS0_10") (pintype "unspecified"))
    )
    (net (code "66") (name "Net-(U10-BS1)") (class "Default")
      (node (ref "R15") (pin "1") (pinfunction "1_1") (pintype "input"))
      (node (ref "U10") (pin "11") (pinfunction "BS1_11") (pintype "unspecified"))
    )
    (net (code "67") (name "Net-(U10-C1N)") (class "Default")
      (node (ref "C6") (pin "1") (pinfunction "1_1") (pintype "unspecified"))
      (node (ref "U10") (pin "5") (pinfunction "C1N_5") (pintype "unspecified"))
    )
    (net (code "68") (name "Net-(U10-C1P)") (class "Default")
      (node (ref "C6") (pin "2") (pinfunction "2_2") (pintype "unspecified"))
      (node (ref "U10") (pin "4") (pinfunction "C1P_4") (pintype "unspecified"))
    )
    (net (code "69") (name "Net-(U10-C2N)") (class "Default")
      (node (ref "C5") (pin "1") (pinfunction "1_1") (pintype "unspecified"))
      (node (ref "U10") (pin "3") (pinfunction "C2N_3") (pintype "unspecified"))
    )
    (net (code "70") (name "Net-(U10-C2P)") (class "Default")
      (node (ref "C5") (pin "2") (pinfunction "2_2") (pintype "unspecified"))
      (node (ref "U10") (pin "2") (pinfunction "C2P_2") (pintype "unspecified"))
    )
    (net (code "71") (name "Net-(U10-IREF)") (class "Default")
      (node (ref "R13") (pin "1") (pinfunction "1_1") (pintype "input"))
      (node (ref "U10") (pin "26") (pinfunction "IREF_26") (pintype "unspecified"))
    )
    (net (code "72") (name "Net-(U10-VCC)") (class "Default")
      (node (ref "C4") (pin "1") (pinfunction "1_1") (pintype "unspecified"))
      (node (ref "U10") (pin "28") (pinfunction "VCC_28") (pintype "unspecified"))
    )
    (net (code "73") (name "Net-(U10-VCOMH)") (class "Default")
      (node (ref "C3") (pin "1") (pinfunction "1_1") (pintype "unspecified"))
      (node (ref "U10") (pin "27") (pinfunction "VCOMH_27") (pintype "unspecified"))
    )
    (net (code "74") (name "VCC_5V") (class "Default")
      (node (ref "U11") (pin "3") (pinfunction "3_3") (pintype "unspecified"))
      (node (ref "U11") (pin "4") (pinfunction "4_4") (pintype "unspecified"))
    )
    (net (code "75") (name "VDD_3V3") (class "Default")
      (node (ref "FPC1") (pin "16") (pinfunction "16_16") (pintype "unspecified"))
      (node (ref "FPC1") (pin "17") (pinfunction "17_17") (pintype "unspecified"))
      (node (ref "FPC1") (pin "18") (pinfunction "18_18") (pintype "unspecified"))
      (node (ref "R10") (pin "2") (pinfunction "2_2") (pintype "input"))
      (node (ref "R11") (pin "2") (pinfunction "2_2") (pintype "input"))
      (node (ref "R14") (pin "2") (pinfunction "2_2") (pintype "input"))
      (node (ref "R17") (pin "1") (pinfunction "1_1") (pintype "input"))
      (node (ref "R19") (pin "1") (pinfunction "1_1") (pintype "input"))
      (node (ref "R3") (pin "2") (pinfunction "2_2") (pintype "input"))
      (node (ref "R4") (pin "1") (pinfunction "1_1") (pintype "input"))
      (node (ref "R6") (pin "1") (pinfunction "1_1") (pintype "input"))
      (node (ref "R7") (pin "1") (pinfunction "1_1") (pintype "input"))
      (node (ref "R8") (pin "2") (pinfunction "2_2") (pintype "input"))
      (node (ref "R9") (pin "2") (pinfunction "2_2") (pintype "input"))
      (node (ref "TP4") (pin "1") (pinfunction "1_1") (pintype "input"))
      (node (ref "U1") (pin "1") (pinfunction "3V3_1") (pintype "unspecified"))
      (node (ref "U10") (pin "6") (pinfunction "VBAT_6") (pintype "unspecified"))
      (node (ref "U10") (pin "9") (pinfunction "VDD_9") (pintype "unspecified"))
      (node (ref "U4") (pin "8") (pinfunction "VCC_8") (pintype "unspecified"))
      (node (ref "U9") (pin "5") (pinfunction "5_5") (pintype "unspecified"))
    )
    (net (code "76") (name "unconnected-(FPC1-Pad25)") (class "Default")
      (node (ref "FPC1") (pin "25") (pinfunction "25_25") (pintype "unspecified+no_connect"))
    )
    (net (code "77") (name "unconnected-(FPC1-Pad26)") (class "Default")
      (node (ref "FPC1") (pin "26") (pinfunction "26_26") (pintype "unspecified+no_connect"))
    )
    (net (code "78") (name "unconnected-(SW5-Pad1)") (class "Default")
      (node (ref "SW5") (pin "1") (pinfunction "1_1") (pintype "unspecified"))
    )
    (net (code "79") (name "unconnected-(SW5-Pad2)") (class "Default")
      (node (ref "SW5") (pin "2") (pinfunction "2_2") (pintype "unspecified"))
    )
    (net (code "80") (name "unconnected-(SW5-PadA)") (class "Default")
      (node (ref "SW5") (pin "A") (pinfunction "A_A") (pintype "unspecified"))
    )
    (net (code "81") (name "unconnected-(SW5-PadB)") (class "Default")
      (node (ref "SW5") (pin "B") (pinfunction "B_B") (pintype "unspecified"))
    )
    (net (code "82") (name "unconnected-(SW5-PadC)") (class "Default")
      (node (ref "SW5") (pin "C") (pinfunction "C_C") (pintype "unspecified"))
    )
    (net (code "83") (name "unconnected-(U1-IO0-Pad18)") (class "Default")
      (node (ref "U1") (pin "18") (pinfunction "IO0_18") (pintype "unspecified+no_connect"))
    )
    (net (code "84") (name "unconnected-(U1-IO1-Pad17)") (class "Default")
      (node (ref "U1") (pin "17") (pinfunction "IO1_17") (pintype "unspecified+no_connect"))
    )
    (net (code "85") (name "unconnected-(U1-IO4-Pad3)") (class "Default")
      (node (ref "U1") (pin "3") (pinfunction "IO4_3") (pintype "unspecified+no_connect"))
    )
    (net (code "86") (name "unconnected-(U1-IO7-Pad6)") (class "Default")
      (node (ref "U1") (pin "6") (pinfunction "IO7_6") (pintype "unspecified+no_connect"))
    )
    (net (code "87") (name "unconnected-(U1-IO10-Pad10)") (class "Default")
      (node (ref "U1") (pin "10") (pinfunction "IO10_10") (pintype "unspecified+no_connect"))
    )
    (net (code "88") (name "unconnected-(U3-BUSJ-Pad18)") (class "Default")
      (node (ref "U3") (pin "18") (pinfunction "BUSJ_18") (pintype "unspecified"))
    )
    (net (code "89") (name "unconnected-(U3-DM1-Pad11)") (class "Default")
      (node (ref "U3") (pin "11") (pinfunction "DM1_11") (pintype "unspecified"))
    )
    (net (code "90") (name "unconnected-(U3-DM2-Pad9)") (class "Default")
      (node (ref "U3") (pin "9") (pinfunction "DM2_9") (pintype "unspecified"))
    )
    (net (code "91") (name "unconnected-(U3-DM3-Pad7)") (class "Default")
      (node (ref "U3") (pin "7") (pinfunction "DM3_7") (pintype "unspecified"))
    )
    (net (code "92") (name "unconnected-(U3-DM4-Pad5)") (class "Default")
      (node (ref "U3") (pin "5") (pinfunction "DM4_5") (pintype "unspecified"))
    )
    (net (code "93") (name "unconnected-(U3-DMU-Pad14)") (class "Default")
      (node (ref "U3") (pin "14") (pinfunction "DMU_14") (pintype "unspecified"))
    )
    (net (code "94") (name "unconnected-(U3-DP1-Pad12)") (class "Default")
      (node (ref "U3") (pin "12") (pinfunction "DP1_12") (pintype "unspecified"))
    )
    (net (code "95") (name "unconnected-(U3-DP2-Pad10)") (class "Default")
      (node (ref "U3") (pin "10") (pinfunction "DP2_10") (pintype "unspecified"))
    )
    (net (code "96") (name "unconnected-(U3-DP3-Pad8)") (class "Default")
      (node (ref "U3") (pin "8") (pinfunction "DP3_8") (pintype "unspecified"))
    )
    (net (code "97") (name "unconnected-(U3-DP4-Pad6)") (class "Default")
      (node (ref "U3") (pin "6") (pinfunction "DP4_6") (pintype "unspecified"))
    )
    (net (code "98") (name "unconnected-(U3-DPU-Pad15)") (class "Default")
      (node (ref "U3") (pin "15") (pinfunction "DPU_15") (pintype "unspecified"))
    )
    (net (code "99") (name "unconnected-(U3-DRV-Pad21)") (class "Default")
      (node (ref "U3") (pin "21") (pinfunction "DRV_21") (pintype "unspecified"))
    )
    (net (code "100") (name "unconnected-(U3-LED1-Pad22)") (class "Default")
      (node (ref "U3") (pin "22") (pinfunction "LED1_22") (pintype "unspecified"))
    )
    (net (code "101") (name "unconnected-(U3-LED2-Pad23)") (class "Default")
      (node (ref "U3") (pin "23") (pinfunction "LED2_23") (pintype "unspecified"))
    )
    (net (code "102") (name "unconnected-(U3-OVCJ-Pad1)") (class "Default")
      (node (ref "U3") (pin "1") (pinfunction "OVCJ_1") (pintype "unspecified"))
    )
    (net (code "103") (name "unconnected-(U3-PWRJ-Pad24)") (class "Default")
      (node (ref "U3") (pin "24") (pinfunction "PWRJ_24") (pintype "unspecified"))
    )
    (net (code "104") (name "unconnected-(U3-REXT-Pad13)") (class "Default")
      (node (ref "U3") (pin "13") (pinfunction "REXT_13") (pintype "unspecified"))
    )
    (net (code "105") (name "unconnected-(U3-TESTJ-Pad2)") (class "Default")
      (node (ref "U3") (pin "2") (pinfunction "TESTJ_2") (pintype "unspecified"))
    )
    (net (code "106") (name "unconnected-(U3-VBUSM-Pad17)") (class "Default")
      (node (ref "U3") (pin "17") (pinfunction "VBUSM_17") (pintype "unspecified"))
    )
    (net (code "107") (name "unconnected-(U3-VD33F-Pad20)") (class "Default")
      (node (ref "U3") (pin "20") (pinfunction "VD33F_20") (pintype "unspecified"))
    )
    (net (code "108") (name "unconnected-(U3-VDD5-Pad19)") (class "Default")
      (node (ref "U3") (pin "19") (pinfunction "VDD5_19") (pintype "unspecified"))
    )
    (net (code "109") (name "unconnected-(U3-VSS-Pad25)") (class "Default")
      (node (ref "U3") (pin "25") (pinfunction "VSS_25") (pintype "unspecified"))
    )
    (net (code "110") (name "unconnected-(U3-XIN-Pad4)") (class "Default")
      (node (ref "U3") (pin "4") (pinfunction "XIN_4") (pintype "unspecified"))
    )
    (net (code "111") (name "unconnected-(U3-XOUT-Pad3)") (class "Default")
      (node (ref "U3") (pin "3") (pinfunction "XOUT_3") (pintype "unspecified"))
    )
    (net (code "112") (name "unconnected-(U3-XRSTJ-Pad16)") (class "Default")
      (node (ref "U3") (pin "16") (pinfunction "XRSTJ_16") (pintype "unspecified"))
    )
    (net (code "113") (name "unconnected-(U8-NC-Pad49)") (class "Default")
      (node (ref "U8") (pin "49") (pinfunction "NC_49") (pintype "unspecified"))
    )
    (net (code "114") (name "unconnected-(U8-NC-Pad73)") (class "Default")
      (node (ref "U8") (pin "73") (pinfunction "NC_73") (pintype "unspecified"))
    )
    (net (code "115") (name "unconnected-(U8-PA0-WKUP-Pad23)") (class "Default")
      (node (ref "U8") (pin "23") (pinfunction "PA0-WKUP_23") (pintype "unspecified"))
    )
    (net (code "116") (name "unconnected-(U8-PA1-Pad24)") (class "Default")
      (node (ref "U8") (pin "24") (pinfunction "PA1_24") (pintype "unspecified"))
    )
    (net (code "117") (name "unconnected-(U8-PA2-Pad25)") (class "Default")
      (node (ref "U8") (pin "25") (pinfunction "PA2_25") (pintype "unspecified"))
    )
    (net (code "118") (name "unconnected-(U8-PA3-Pad26)") (class "Default")
      (node (ref "U8") (pin "26") (pinfunction "PA3_26") (pintype "unspecified"))
    )
    (net (code "119") (name "unconnected-(U8-PA5-Pad30)") (class "Default")
      (node (ref "U8") (pin "30") (pinfunction "PA5_30") (pintype "unspecified"))
    )
    (net (code "120") (name "unconnected-(U8-PA8-Pad67)") (class "Default")
      (node (ref "U8") (pin "67") (pinfunction "PA8_67") (pintype "unspecified"))
    )
    (net (code "121") (name "unconnected-(U8-PA12-Pad71)") (class "Default")
      (node (ref "U8") (pin "71") (pinfunction "PA12_71") (pintype "unspecified"))
    )
    (net (code "122") (name "unconnected-(U8-PA15-Pad77)") (class "Default")
      (node (ref "U8") (pin "77") (pinfunction "PA15_77") (pintype "unspecified"))
    )
    (net (code "123") (name "unconnected-(U8-PB8-Pad95)") (class "Default")
      (node (ref "U8") (pin "95") (pinfunction "PB8_95") (pintype "unspecified"))
    )
    (net (code "124") (name "unconnected-(U8-PB9-Pad96)") (class "Default")
      (node (ref "U8") (pin "96") (pinfunction "PB9_96") (pintype "unspecified"))
    )
    (net (code "125") (name "unconnected-(U8-PB10-Pad47)") (class "Default")
      (node (ref "U8") (pin "47") (pinfunction "PB10_47") (pintype "unspecified"))
    )
    (net (code "126") (name "unconnected-(U8-PB11-Pad48)") (class "Default")
      (node (ref "U8") (pin "48") (pinfunction "PB11_48") (pintype "unspecified"))
    )
    (net (code "127") (name "unconnected-(U8-PC0-Pad15)") (class "Default")
      (node (ref "U8") (pin "15") (pinfunction "PC0_15") (pintype "unspecified"))
    )
    (net (code "128") (name "unconnected-(U8-PC1-Pad16)") (class "Default")
      (node (ref "U8") (pin "16") (pinfunction "PC1_16") (pintype "unspecified"))
    )
    (net (code "129") (name "unconnected-(U8-PC2-Pad17)") (class "Default")
      (node (ref "U8") (pin "17") (pinfunction "PC2_17") (pintype "unspecified"))
    )
    (net (code "130") (name "unconnected-(U8-PC3-Pad18)") (class "Default")
      (node (ref "U8") (pin "18") (pinfunction "PC3_18") (pintype "unspecified"))
    )
    (net (code "131") (name "unconnected-(U8-PC6-Pad63)") (class "Default")
      (node (ref "U8") (pin "63") (pinfunction "PC6_63") (pintype "unspecified"))
    )
    (net (code "132") (name "unconnected-(U8-PC7-Pad64)") (class "Default")
      (node (ref "U8") (pin "64") (pinfunction "PC7_64") (pintype "unspecified"))
    )
    (net (code "133") (name "unconnected-(U8-PC8-Pad65)") (class "Default")
      (node (ref "U8") (pin "65") (pinfunction "PC8_65") (pintype "unspecified"))
    )
    (net (code "134") (name "unconnected-(U8-PC9-Pad66)") (class "Default")
      (node (ref "U8") (pin "66") (pinfunction "PC9_66") (pintype "unspecified"))
    )
    (net (code "135") (name "unconnected-(U8-PC13-TAMPER-RTC-Pad7)") (class "Default")
      (node (ref "U8") (pin "7") (pinfunction "PC13-TAMPER-RTC_7") (pintype "unspecified"))
    )
    (net (code "136") (name "unconnected-(U8-PC14-OSC32IN-Pad8)") (class "Default")
      (node (ref "U8") (pin "8") (pinfunction "PC14-OSC32IN_8") (pintype "unspecified"))
    )
    (net (code "137") (name "unconnected-(U8-PC15-OSC32OUT-Pad9)") (class "Default")
      (node (ref "U8") (pin "9") (pinfunction "PC15-OSC32OUT_9") (pintype "unspecified"))
    )
    (net (code "138") (name "unconnected-(U8-PD2-Pad83)") (class "Default")
      (node (ref "U8") (pin "83") (pinfunction "PD2_83") (pintype "unspecified"))
    )
    (net (code "139") (name "unconnected-(U8-PD8-Pad55)") (class "Default")
      (node (ref "U8") (pin "55") (pinfunction "PD8_55") (pintype "unspecified"))
    )
    (net (code "140") (name "unconnected-(U8-PD9-Pad56)") (class "Default")
      (node (ref "U8") (pin "56") (pinfunction "PD9_56") (pintype "unspecified"))
    )
    (net (code "141") (name "unconnected-(U8-PD10-Pad57)") (class "Default")
      (node (ref "U8") (pin "57") (pinfunction "PD10_57") (pintype "unspecified"))
    )
    (net (code "142") (name "unconnected-(U8-PD11-Pad58)") (class "Default")
      (node (ref "U8") (pin "58") (pinfunction "PD11_58") (pintype "unspecified"))
    )
    (net (code "143") (name "unconnected-(U8-PD12-Pad59)") (class "Default")
      (node (ref "U8") (pin "59") (pinfunction "PD12_59") (pintype "unspecified"))
    )
    (net (code "144") (name "unconnected-(U8-PD13-Pad60)") (class "Default")
      (node (ref "U8") (pin "60") (pinfunction "PD13_60") (pintype "unspecified"))
    )
    (net (code "145") (name "unconnected-(U8-PD14-Pad61)") (class "Default")
      (node (ref "U8") (pin "61") (pinfunction "PD14_61") (pintype "unspecified"))
    )
    (net (code "146") (name "unconnected-(U8-PD15-Pad62)") (class "Default")
      (node (ref "U8") (pin "62") (pinfunction "PD15_62") (pintype "unspecified"))
    )
    (net (code "147") (name "unconnected-(U8-PE0-Pad97)") (class "Default")
      (node (ref "U8") (pin "97") (pinfunction "PE0_97") (pintype "unspecified"))
    )
    (net (code "148") (name "unconnected-(U8-PE1-Pad98)") (class "Default")
      (node (ref "U8") (pin "98") (pinfunction "PE1_98") (pintype "unspecified"))
    )
    (net (code "149") (name "unconnected-(U8-PE2-Pad1)") (class "Default")
      (node (ref "U8") (pin "1") (pinfunction "PE2_1") (pintype "unspecified"))
    )
    (net (code "150") (name "unconnected-(U8-PE3-Pad2)") (class "Default")
      (node (ref "U8") (pin "2") (pinfunction "PE3_2") (pintype "unspecified"))
    )
    (net (code "151") (name "unconnected-(U8-PE4-Pad3)") (class "Default")
      (node (ref "U8") (pin "3") (pinfunction "PE4_3") (pintype "unspecified"))
    )
    (net (code "152") (name "unconnected-(U8-PE5-Pad4)") (class "Default")
      (node (ref "U8") (pin "4") (pinfunction "PE5_4") (pintype "unspecified"))
    )
    (net (code "153") (name "unconnected-(U8-PE6-Pad5)") (class "Default")
      (node (ref "U8") (pin "5") (pinfunction "PE6_5") (pintype "unspecified"))
    )
    (net (code "154") (name "unconnected-(U8-PE12-Pad43)") (class "Default")
      (node (ref "U8") (pin "43") (pinfunction "PE12_43") (pintype "unspecified"))
    )
    (net (code "155") (name "unconnected-(U8-PE13-Pad44)") (class "Default")
      (node (ref "U8") (pin "44") (pinfunction "PE13_44") (pintype "unspecified"))
    )
    (net (code "156") (name "unconnected-(U8-PE14-Pad45)") (class "Default")
      (node (ref "U8") (pin "45") (pinfunction "PE14_45") (pintype "unspecified"))
    )
    (net (code "157") (name "unconnected-(U8-PE15-Pad46)") (class "Default")
      (node (ref "U8") (pin "46") (pinfunction "PE15_46") (pintype "unspecified"))
    )
    (net (code "158") (name "unconnected-(U8-VBAT-Pad6)") (class "Default")
      (node (ref "U8") (pin "6") (pinfunction "VBAT_6") (pintype "unspecified"))
    )
    (net (code "159") (name "unconnected-(U8-VDD-Pad11)") (class "Default")
      (node (ref "U8") (pin "11") (pinfunction "VDD_11") (pintype "unspecified"))
    )
    (net (code "160") (name "unconnected-(U8-VDD-Pad19)") (class "Default")
      (node (ref "U8") (pin "19") (pinfunction "VDD_19") (pintype "unspecified"))
    )
    (net (code "161") (name "unconnected-(U8-VDD-Pad28)") (class "Default")
      (node (ref "U8") (pin "28") (pinfunction "VDD_28") (pintype "unspecified"))
    )
    (net (code "162") (name "unconnected-(U8-VDD-Pad50)") (class "Default")
      (node (ref "U8") (pin "50") (pinfunction "VDD_50") (pintype "unspecified"))
    )
    (net (code "163") (name "unconnected-(U8-VDD-Pad75)") (class "Default")
      (node (ref "U8") (pin "75") (pinfunction "VDD_75") (pintype "unspecified"))
    )
    (net (code "164") (name "unconnected-(U8-VDD-Pad100)") (class "Default")
      (node (ref "U8") (pin "100") (pinfunction "VDD_100") (pintype "unspecified"))
    )
    (net (code "165") (name "unconnected-(U8-VDDA-Pad22)") (class "Default")
      (node (ref "U8") (pin "22") (pinfunction "VDDA_22") (pintype "unspecified"))
    )
    (net (code "166") (name "unconnected-(U8-VREF+-Pad21)") (class "Default")
      (node (ref "U8") (pin "21") (pinfunction "VREF+_21") (pintype "unspecified"))
    )
    (net (code "167") (name "unconnected-(U8-VSS-Pad10)") (class "Default")
      (node (ref "U8") (pin "10") (pinfunction "VSS_10") (pintype "unspecified"))
    )
    (net (code "168") (name "unconnected-(U8-VSS-Pad27)") (class "Default")
      (node (ref "U8") (pin "27") (pinfunction "VSS_27") (pintype "unspecified"))
    )
    (net (code "169") (name "unconnected-(U8-VSS-Pad74)") (class "Default")
      (node (ref "U8") (pin "74") (pinfunction "VSS_74") (pintype "unspecified"))
    )
    (net (code "170") (name "unconnected-(U8-VSS-Pad99)") (class "Default")
      (node (ref "U8") (pin "99") (pinfunction "VSS_99") (pintype "unspecified"))
    )
    (net (code "171") (name "unconnected-(U8-VSSA-Pad20)") (class "Default")
      (node (ref "U8") (pin "20") (pinfunction "VSSA_20") (pintype "unspecified"))
    )
    (net (code "172") (name "unconnected-(U9-Pad9)") (class "Default")
      (node (ref "U9") (pin "9") (pinfunction "9_9") (pintype "unspecified+no_connect"))
    )
    (net (code "173") (name "unconnected-(U9-Pad10)") (class "Default")
      (node (ref "U9") (pin "10") (pinfunction "10_10") (pintype "unspecified+no_connect"))
    )
    (net (code "174") (name "unconnected-(U10-N.C.-Pad7)") (class "Default")
      (node (ref "U10") (pin "7") (pinfunction "N.C._7") (pintype "unspecified+no_connect"))
    )
    (net (code "175") (name "unconnected-(U11-Pad5)") (class "Default")
      (node (ref "U11") (pin "5") (pinfunction "5_5") (pintype "unspecified+no_connect"))
    )
    (net (code "176") (name "unconnected-(U11-Pad6)") (class "Default")
      (node (ref "U11") (pin "6") (pinfunction "6_6") (pintype "unspecified+no_connect"))
    )
    (net (code "177") (name "unconnected-(U12-EN#-Pad2)") (class "Default")
      (node (ref "U12") (pin "2") (pinfunction "EN#_2") (pintype "unspecified"))
    )
    (net (code "178") (name "unconnected-(U12-FB{slash}NC-Pad7)") (class "Default")
      (node (ref "U12") (pin "7") (pinfunction "FB/NC_7") (pintype "unspecified"))
    )
    (net (code "179") (name "unconnected-(U12-GND-Pad1)") (class "Default")
      (node (ref "U12") (pin "1") (pinfunction "GND_1") (pintype "unspecified"))
    )
    (net (code "180") (name "unconnected-(U12-IN-Pad3)") (class "Default")
      (node (ref "U12") (pin "3") (pinfunction "IN_3") (pintype "unspecified"))
    )
    (net (code "181") (name "unconnected-(U12-IN-Pad4)") (class "Default")
      (node (ref "U12") (pin "4") (pinfunction "IN_4") (pintype "unspecified"))
    )
    (net (code "182") (name "unconnected-(U12-OUT-Pad5)") (class "Default")
      (node (ref "U12") (pin "5") (pinfunction "OUT_5") (pintype "unspecified"))
    )
    (net (code "183") (name "unconnected-(U12-OUT-Pad6)") (class "Default")
      (node (ref "U12") (pin "6") (pinfunction "OUT_6") (pintype "unspecified"))
    )
    (net (code "184") (name "unconnected-(U12-PG-Pad8)") (class "Default")
      (node (ref "U12") (pin "8") (pinfunction "PG_8") (pintype "unspecified"))
    )
    (net (code "185") (name "unconnected-(U13-GND-Pad3)") (class "Default")
      (node (ref "U13") (pin "3") (pinfunction "GND_3") (pintype "unspecified"))
    )
    (net (code "186") (name "unconnected-(U13-VDD-Pad1)") (class "Default")
      (node (ref "U13") (pin "1") (pinfunction "VDD_1") (pintype "unspecified"))
    )
    (net (code "187") (name "unconnected-(U13-VOUT-Pad2)") (class "Default")
      (node (ref "U13") (pin "2") (pinfunction "VOUT_2") (pintype "unspecified"))
    )
    (net (code "188") (name "unconnected-(U14-GND-Pad3)") (class "Default")
      (node (ref "U14") (pin "3") (pinfunction "GND_3") (pintype "unspecified"))
    )
    (net (code "189") (name "unconnected-(U14-VDD-Pad1)") (class "Default")
      (node (ref "U14") (pin "1") (pinfunction "VDD_1") (pintype "unspecified"))
    )
    (net (code "190") (name "unconnected-(U14-VOUT-Pad2)") (class "Default")
      (node (ref "U14") (pin "2") (pinfunction "VOUT_2") (pintype "unspecified"))
    )
    (net (code "191") (name "unconnected-(USB1-CC1-PadA5)") (class "Default")
      (node (ref "USB1") (pin "A5") (pinfunction "CC1_A5") (pintype "unspecified"))
    )
    (net (code "192") (name "unconnected-(USB1-CC2-PadB5)") (class "Default")
      (node (ref "USB1") (pin "B5") (pinfunction "CC2_B5") (pintype "unspecified"))
    )
    (net (code "193") (name "unconnected-(USB1-DN1-PadA7)") (class "Default")
      (node (ref "USB1") (pin "A7") (pinfunction "DN1_A7") (pintype "unspecified"))
    )
    (net (code "194") (name "unconnected-(USB1-DN2-PadB7)") (class "Default")
      (node (ref "USB1") (pin "B7") (pinfunction "DN2_B7") (pintype "unspecified"))
    )
    (net (code "195") (name "unconnected-(USB1-DP1-PadA6)") (class "Default")
      (node (ref "USB1") (pin "A6") (pinfunction "DP1_A6") (pintype "unspecified"))
    )
    (net (code "196") (name "unconnected-(USB1-DP2-PadB6)") (class "Default")
      (node (ref "USB1") (pin "B6") (pinfunction "DP2_B6") (pintype "unspecified"))
    )
    (net (code "197") (name "unconnected-(USB1-GND-Pad12)") (class "Default")
      (node (ref "USB1") (pin "12") (pinfunction "GND_12") (pintype "unspecified"))
    )
    (net (code "198") (name "unconnected-(USB1-GND-Pad13)") (class "Default")
      (node (ref "USB1") (pin "13") (pinfunction "GND_13") (pintype "unspecified"))
    )
    (net (code "199") (name "unconnected-(USB1-GND-Pad14)") (class "Default")
      (node (ref "USB1") (pin "14") (pinfunction "GND_14") (pintype "unspecified"))
    )
    (net (code "200") (name "unconnected-(USB1-GND-Pad15)") (class "Default")
      (node (ref "USB1") (pin "15") (pinfunction "GND_15") (pintype "unspecified"))
    )
    (net (code "201") (name "unconnected-(USB1-GND-PadA1B12)") (class "Default")
      (node (ref "USB1") (pin "A1B12") (pinfunction "GND_A1B12") (pintype "unspecified"))
    )
    (net (code "202") (name "unconnected-(USB1-GND-PadB1A12)") (class "Default")
      (node (ref "USB1") (pin "B1A12") (pinfunction "GND_B1A12") (pintype "unspecified"))
    )
    (net (code "203") (name "unconnected-(USB1-SBU1-PadA8)") (class "Default")
      (node (ref "USB1") (pin "A8") (pinfunction "SBU1_A8") (pintype "unspecified"))
    )
    (net (code "204") (name "unconnected-(USB1-SBU2-PadB8)") (class "Default")
      (node (ref "USB1") (pin "B8") (pinfunction "SBU2_B8") (pintype "unspecified"))
    )
    (net (code "205") (name "unconnected-(USB1-VBUS-PadA4B9)") (class "Default")
      (node (ref "USB1") (pin "A4B9") (pinfunction "VBUS_A4B9") (pintype "unspecified"))
    )
    (net (code "206") (name "unconnected-(USB1-VBUS-PadB4A9)") (class "Default")
      (node (ref "USB1") (pin "B4A9") (pinfunction "VBUS_B4A9") (pintype "unspecified"))
    )
  )
)
